# MCU.net
KiCad netlist of a schematic drawn in Altium Designer
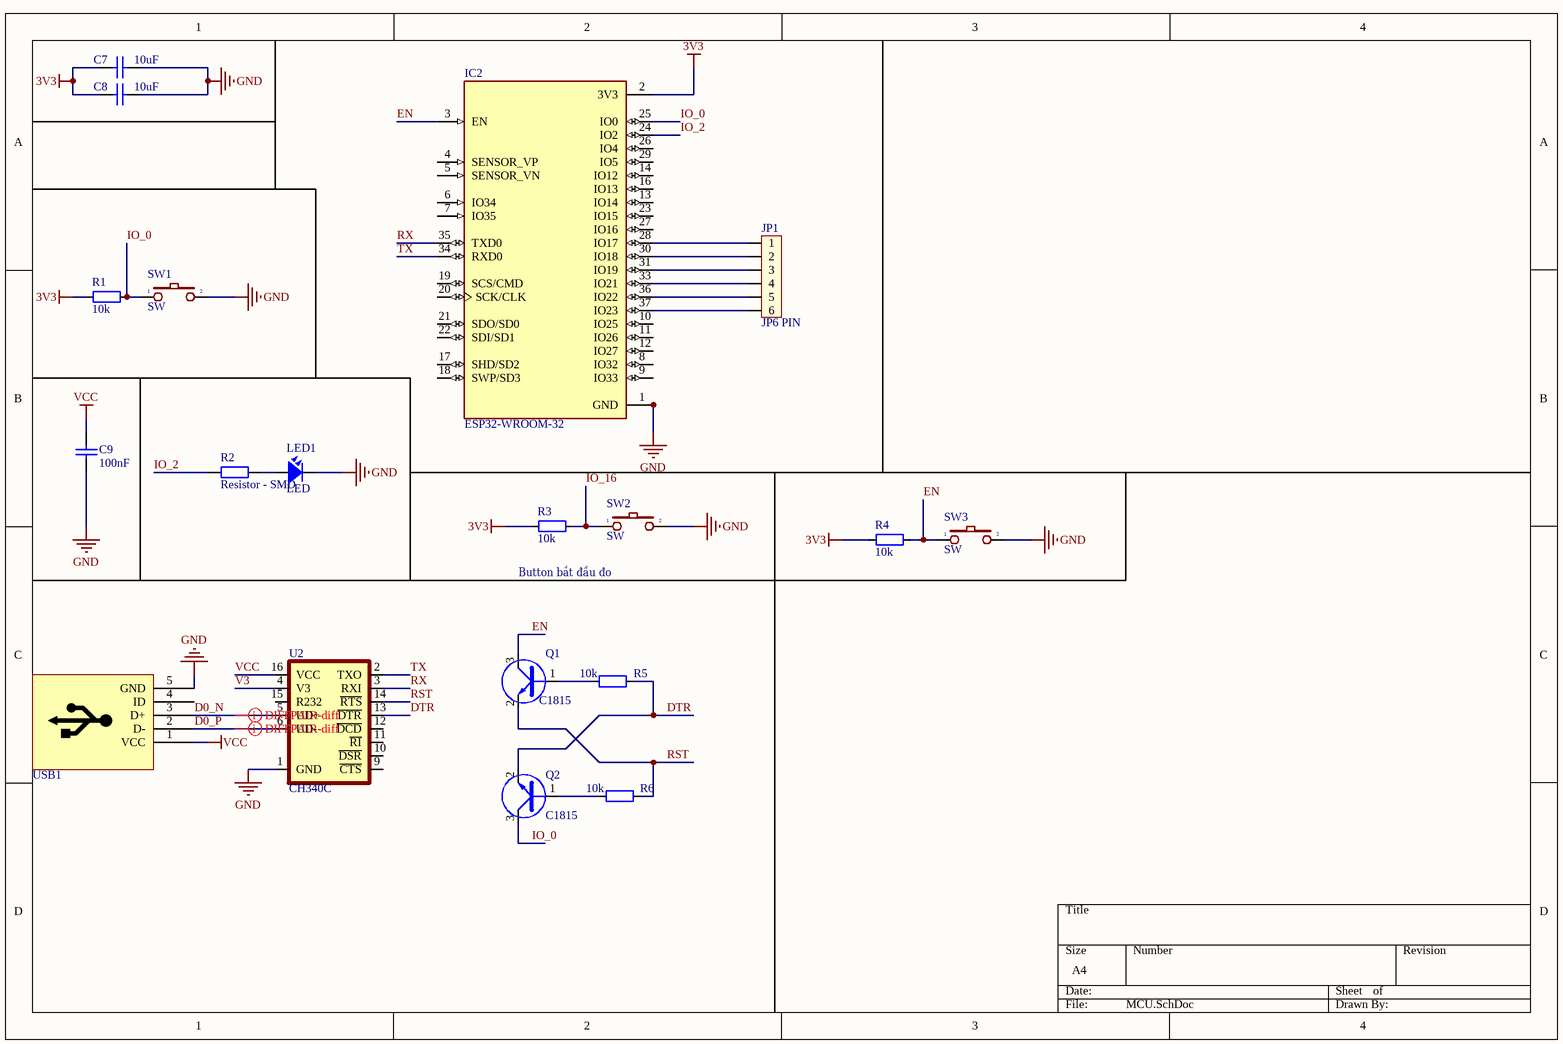
[diagram p0: MCU.SchDoc]

(export (version "E")
  (design (tool "Eeschema 10.0.6"))
  (components
    (comp (ref "C7")
      (value "10uF")
      (footprint "C0805")
      (description "Capacitor")
      (fields (field (name "PUBLISHER") "Altium Limited"))
      (libsource (lib "My Library") (part "CapSMD"))
    )
    (comp (ref "C8")
      (value "10uF")
      (footprint "C0805")
      (description "Capacitor")
      (fields (field (name "PUBLISHER") "Altium Limited"))
      (libsource (lib "My Library") (part "CapSMD"))
    )
    (comp (ref "C9")
      (value "100nF")
      (footprint "C0805")
      (description "Capacitor")
      (fields (field (name "PUBLISHER") "Altium Limited"))
      (libsource (lib "My Library") (part "CapSMD"))
    )
    (comp (ref "IC2")
      (value "ESP32-WROOM-32")
      (footprint "MODULE_ESP32-WROOM-32")
      (description "Bluetooth, WiFi Transceiver Module 2.4GHz ~ 2.5GHz Surface Mount")
      (fields (field (name "MF") "Espressif Systems") (field (name "DIGI-KEY_PART_NUMBER") "1904-1010-1-ND"))
      (libsource (lib "Main") (part "ESP32-WROOM-32"))
    )
    (comp (ref "JP1") (value "JP6 PIN") (footprint "JP6") (libsource (lib "Main") (part "JP6")))
    (comp (ref "LED1")
      (value "LED")
      (footprint "LED0805")
      (description "LED Single colour Green and Red")
      (libsource (lib "Main") (part "LED"))
    )
    (comp (ref "Q1")
      (value "C1815")
      (footprint "SOT23D")
      (description "NPN 600mW, ECB")
      (libsource (lib "My Library") (part "2SC1815"))
    )
    (comp (ref "Q2")
      (value "C1815")
      (footprint "SOT23D")
      (description "NPN 600mW, ECB")
      (libsource (lib "") (part "2SC1815_1"))
    )
    (comp (ref "R1")
      (value "10k")
      (footprint "RES-SMD-0805")
      (description "Resistor")
      (fields
        (field (name "MANUFACTURER") "Generic Components")
        (field (name "PUBLISHER") "Altium Hobart Technology Centre")
      )
      (libsource (lib "My Library") (part "Resistor - SMD"))
    )
    (comp (ref "R2")
      (value "Resistor - SMD")
      (footprint "RES-SMD-0805")
      (description "Resistor SMD")
      (fields
        (field (name "MANUFACTURER") "Generic Components")
        (field (name "PUBLISHER") "Altium Hobart Technology Centre")
      )
      (libsource (lib "Main") (part "Resistor - SMD"))
    )
    (comp (ref "R3")
      (value "10k")
      (footprint "RES-SMD-0805")
      (description "Resistor")
      (fields
        (field (name "MANUFACTURER") "Generic Components")
        (field (name "PUBLISHER") "Altium Hobart Technology Centre")
      )
      (libsource (lib "My Library") (part "Resistor - SMD"))
    )
    (comp (ref "R4")
      (value "10k")
      (footprint "RES-SMD-0805")
      (description "Resistor")
      (fields
        (field (name "MANUFACTURER") "Generic Components")
        (field (name "PUBLISHER") "Altium Hobart Technology Centre")
      )
      (libsource (lib "My Library") (part "Resistor - SMD"))
    )
    (comp (ref "R5")
      (value "10k")
      (footprint "RES-SMD-0805")
      (description "Resistor")
      (fields
        (field (name "MANUFACTURER") "Generic Components")
        (field (name "PUBLISHER") "Altium Hobart Technology Centre")
      )
      (libsource (lib "My Library") (part "Resistor - SMD"))
    )
    (comp (ref "R6")
      (value "10k")
      (footprint "RES-SMD-0805")
      (description "Resistor")
      (fields
        (field (name "MANUFACTURER") "Generic Components")
        (field (name "PUBLISHER") "Altium Hobart Technology Centre")
      )
      (libsource (lib "My Library") (part "Resistor - SMD"))
    )
    (comp (ref "SW1")
      (value "SW")
      (footprint "SW2")
      (description "Switch button 2 pin")
      (libsource (lib "My Library") (part "SW2"))
    )
    (comp (ref "SW2")
      (value "SW")
      (footprint "SW2")
      (description "Switch button 2 pin")
      (libsource (lib "My Library") (part "SW2"))
    )
    (comp (ref "SW3")
      (value "SW")
      (footprint "SW2")
      (description "Switch button 2 pin")
      (libsource (lib "My Library") (part "SW2"))
    )
    (comp (ref "U2")
      (value "CH340C")
      (footprint "SOP-16")
      (description "USB to serial chip CH340")
      (fields (field (name "MF") "WCH"))
      (libsource (lib "My Library") (part "CH340C"))
    )
    (comp (ref "USB1") (value "USB") (footprint "USB-M1") (libsource (lib "My Library") (part "USB-M")))
  )
  (nets
    (net (code "1") (name "/D0_N") (class "Default")
      (node (ref "U2") (pin "5") (pinfunction "UD+_5") (pintype "bidirectional"))
      (node (ref "USB1") (pin "3") (pinfunction "D+_3") (pintype "passive"))
    )
    (net (code "2") (name "/D0_P") (class "Default")
      (node (ref "U2") (pin "6") (pinfunction "UD-_6") (pintype "bidirectional"))
      (node (ref "USB1") (pin "2") (pinfunction "D-_2") (pintype "passive"))
    )
    (net (code "3") (name "/DTR") (class "Default")
      (node (ref "Q2") (pin "2") (pinfunction "E_2") (pintype "passive"))
      (node (ref "R5") (pin "1") (pinfunction "1_1") (pintype "passive"))
      (node (ref "U2") (pin "13") (pinfunction "~{DTR}_13") (pintype "bidirectional"))
    )
    (net (code "4") (name "/EN") (class "Default")
      (node (ref "IC2") (pin "3") (pinfunction "EN_3") (pintype "input"))
      (node (ref "Q1") (pin "3") (pinfunction "C_3") (pintype "passive"))
      (node (ref "R4") (pin "1") (pinfunction "1_1") (pintype "passive"))
      (node (ref "SW3") (pin "1") (pinfunction "1_1") (pintype "passive"))
    )
    (net (code "5") (name "/IO_0") (class "Default")
      (node (ref "IC2") (pin "25") (pinfunction "IO0_25") (pintype "bidirectional"))
      (node (ref "Q2") (pin "3") (pinfunction "C_3") (pintype "passive"))
      (node (ref "R1") (pin "1") (pinfunction "1_1") (pintype "passive"))
      (node (ref "SW1") (pin "1") (pinfunction "1_1") (pintype "passive"))
    )
    (net (code "6") (name "/IO_2") (class "Default")
      (node (ref "IC2") (pin "24") (pinfunction "IO2_24") (pintype "bidirectional"))
      (node (ref "R2") (pin "2") (pinfunction "2_2") (pintype "passive"))
    )
    (net (code "7") (name "/IO_16") (class "Default")
      (node (ref "R3") (pin "1") (pinfunction "1_1") (pintype "passive"))
      (node (ref "SW2") (pin "1") (pinfunction "1_1") (pintype "passive"))
    )
    (net (code "8") (name "/RST") (class "Default")
      (node (ref "Q1") (pin "2") (pinfunction "E_2") (pintype "passive"))
      (node (ref "R6") (pin "1") (pinfunction "1_1") (pintype "passive"))
      (node (ref "U2") (pin "14") (pinfunction "~{RTS}_14") (pintype "bidirectional"))
    )
    (net (code "9") (name "/RX") (class "Default")
      (node (ref "IC2") (pin "35") (pinfunction "TXD0_35") (pintype "bidirectional"))
      (node (ref "U2") (pin "3") (pinfunction "RXI_3") (pintype "bidirectional"))
    )
    (net (code "10") (name "/TX") (class "Default")
      (node (ref "IC2") (pin "34") (pinfunction "RXD0_34") (pintype "bidirectional"))
      (node (ref "U2") (pin "2") (pinfunction "TXO_2") (pintype "bidirectional"))
    )
    (net (code "11") (name "/V3") (class "Default")
      (node (ref "U2") (pin "4") (pinfunction "V3_4") (pintype "bidirectional"))
    )
    (net (code "12") (name "3V3") (class "Default")
      (node (ref "C7") (pin "1") (pinfunction "1_1") (pintype "passive"))
      (node (ref "C8") (pin "1") (pinfunction "1_1") (pintype "passive"))
      (node (ref "IC2") (pin "2") (pinfunction "3V3_2") (pintype "power_in"))
      (node (ref "R1") (pin "2") (pinfunction "2_2") (pintype "passive"))
      (node (ref "R3") (pin "2") (pinfunction "2_2") (pintype "passive"))
      (node (ref "R4") (pin "2") (pinfunction "2_2") (pintype "passive"))
    )
    (net (code "13") (name "GND") (class "Default")
      (node (ref "C7") (pin "2") (pinfunction "2_2") (pintype "passive"))
      (node (ref "C8") (pin "2") (pinfunction "2_2") (pintype "passive"))
      (node (ref "C9") (pin "1") (pinfunction "1_1") (pintype "passive"))
      (node (ref "IC2") (pin "1") (pinfunction "GND_1") (pintype "power_in"))
      (node (ref "IC2") (pin "15") (pinfunction "GND_15") (pintype "power_in"))
      (node (ref "IC2") (pin "38") (pinfunction "GND_38") (pintype "power_in"))
      (node (ref "IC2") (pin "39_1") (pinfunction "GND_39_1") (pintype "power_in"))
      (node (ref "IC2") (pin "39_10") (pinfunction "GND_39_10") (pintype "power_in"))
      (node (ref "IC2") (pin "39_11") (pinfunction "GND_39_11") (pintype "power_in"))
      (node (ref "IC2") (pin "39_12") (pinfunction "GND_39_12") (pintype "power_in"))
      (node (ref "IC2") (pin "39_13") (pinfunction "GND_39_13") (pintype "power_in"))
      (node (ref "IC2") (pin "39_14") (pinfunction "GND_39_14") (pintype "power_in"))
      (node (ref "IC2") (pin "39_15") (pinfunction "GND_39_15") (pintype "power_in"))
      (node (ref "IC2") (pin "39_16") (pinfunction "GND_39_16") (pintype "power_in"))
      (node (ref "IC2") (pin "39_17") (pinfunction "GND_39_17") (pintype "power_in"))
      (node (ref "IC2") (pin "39_18") (pinfunction "GND_39_18") (pintype "power_in"))
      (node (ref "IC2") (pin "39_19") (pinfunction "GND_39_19") (pintype "power_in"))
      (node (ref "IC2") (pin "39_2") (pinfunction "GND_39_2") (pintype "power_in"))
      (node (ref "IC2") (pin "39_20") (pinfunction "GND_39_20") (pintype "power_in"))
      (node (ref "IC2") (pin "39_21") (pinfunction "GND_39_21") (pintype "power_in"))
      (node (ref "IC2") (pin "39_3") (pinfunction "GND_39_3") (pintype "power_in"))
      (node (ref "IC2") (pin "39_4") (pinfunction "GND_39_4") (pintype "power_in"))
      (node (ref "IC2") (pin "39_5") (pinfunction "GND_39_5") (pintype "power_in"))
      (node (ref "IC2") (pin "39_6") (pinfunction "GND_39_6") (pintype "power_in"))
      (node (ref "IC2") (pin "39_7") (pinfunction "GND_39_7") (pintype "power_in"))
      (node (ref "IC2") (pin "39_8") (pinfunction "GND_39_8") (pintype "power_in"))
      (node (ref "IC2") (pin "39_9") (pinfunction "GND_39_9") (pintype "power_in"))
      (node (ref "LED1") (pin "2") (pinfunction "2_2") (pintype "passive"))
      (node (ref "SW1") (pin "2") (pinfunction "2_2") (pintype "passive"))
      (node (ref "SW2") (pin "2") (pinfunction "2_2") (pintype "passive"))
      (node (ref "SW3") (pin "2") (pinfunction "2_2") (pintype "passive"))
      (node (ref "U2") (pin "1") (pinfunction "GND_1") (pintype "bidirectional"))
      (node (ref "USB1") (pin "5") (pinfunction "GND_5") (pintype "passive"))
    )
    (net (code "14") (name "Net-(IC2-IO17)") (class "Default")
      (node (ref "IC2") (pin "28") (pinfunction "IO17_28") (pintype "bidirectional"))
      (node (ref "JP1") (pin "1") (pinfunction "1_1") (pintype "passive"))
    )
    (net (code "15") (name "Net-(IC2-IO18)") (class "Default")
      (node (ref "IC2") (pin "30") (pinfunction "IO18_30") (pintype "bidirectional"))
      (node (ref "JP1") (pin "2") (pinfunction "2_2") (pintype "passive"))
    )
    (net (code "16") (name "Net-(IC2-IO19)") (class "Default")
      (node (ref "IC2") (pin "31") (pinfunction "IO19_31") (pintype "bidirectional"))
      (node (ref "JP1") (pin "3") (pinfunction "3_3") (pintype "passive"))
    )
    (net (code "17") (name "Net-(IC2-IO21)") (class "Default")
      (node (ref "IC2") (pin "33") (pinfunction "IO21_33") (pintype "bidirectional"))
      (node (ref "JP1") (pin "4") (pinfunction "4_4") (pintype "passive"))
    )
    (net (code "18") (name "Net-(IC2-IO22)") (class "Default")
      (node (ref "IC2") (pin "36") (pinfunction "IO22_36") (pintype "bidirectional"))
      (node (ref "JP1") (pin "5") (pinfunction "5_5") (pintype "passive"))
    )
    (net (code "19") (name "Net-(IC2-IO23)") (class "Default")
      (node (ref "IC2") (pin "37") (pinfunction "IO23_37") (pintype "bidirectional"))
      (node (ref "JP1") (pin "6") (pinfunction "6_6") (pintype "passive"))
    )
    (net (code "20") (name "Net-(LED1-Pad1)") (class "Default")
      (node (ref "LED1") (pin "1") (pinfunction "1_1") (pintype "passive"))
      (node (ref "R2") (pin "1") (pinfunction "1_1") (pintype "passive"))
    )
    (net (code "21") (name "Net-(Q1-B)") (class "Default")
      (node (ref "Q1") (pin "1") (pinfunction "B_1") (pintype "passive"))
      (node (ref "R5") (pin "2") (pinfunction "2_2") (pintype "passive"))
    )
    (net (code "22") (name "Net-(Q2-B)") (class "Default")
      (node (ref "Q2") (pin "1") (pinfunction "B_1") (pintype "passive"))
      (node (ref "R6") (pin "2") (pinfunction "2_2") (pintype "passive"))
    )
    (net (code "23") (name "VCC") (class "Default")
      (node (ref "C9") (pin "2") (pinfunction "2_2") (pintype "passive"))
      (node (ref "U2") (pin "16") (pinfunction "VCC_16") (pintype "bidirectional"))
      (node (ref "USB1") (pin "1") (pinfunction "VCC_1") (pintype "passive"))
    )
    (net (code "24") (name "unconnected-(IC2-IO4-Pad26)") (class "Default")
      (node (ref "IC2") (pin "26") (pinfunction "IO4_26") (pintype "bidirectional"))
    )
    (net (code "25") (name "unconnected-(IC2-IO5-Pad29)") (class "Default")
      (node (ref "IC2") (pin "29") (pinfunction "IO5_29") (pintype "bidirectional"))
    )
    (net (code "26") (name "unconnected-(IC2-IO12-Pad14)") (class "Default")
      (node (ref "IC2") (pin "14") (pinfunction "IO12_14") (pintype "bidirectional"))
    )
    (net (code "27") (name "unconnected-(IC2-IO13-Pad16)") (class "Default")
      (node (ref "IC2") (pin "16") (pinfunction "IO13_16") (pintype "bidirectional"))
    )
    (net (code "28") (name "unconnected-(IC2-IO14-Pad13)") (class "Default")
      (node (ref "IC2") (pin "13") (pinfunction "IO14_13") (pintype "bidirectional"))
    )
    (net (code "29") (name "unconnected-(IC2-IO15-Pad23)") (class "Default")
      (node (ref "IC2") (pin "23") (pinfunction "IO15_23") (pintype "bidirectional"))
    )
    (net (code "30") (name "unconnected-(IC2-IO16-Pad27)") (class "Default")
      (node (ref "IC2") (pin "27") (pinfunction "IO16_27") (pintype "bidirectional"))
    )
    (net (code "31") (name "unconnected-(IC2-IO25-Pad10)") (class "Default")
      (node (ref "IC2") (pin "10") (pinfunction "IO25_10") (pintype "bidirectional"))
    )
    (net (code "32") (name "unconnected-(IC2-IO26-Pad11)") (class "Default")
      (node (ref "IC2") (pin "11") (pinfunction "IO26_11") (pintype "bidirectional"))
    )
    (net (code "33") (name "unconnected-(IC2-IO27-Pad12)") (class "Default")
      (node (ref "IC2") (pin "12") (pinfunction "IO27_12") (pintype "bidirectional"))
    )
    (net (code "34") (name "unconnected-(IC2-IO32-Pad8)") (class "Default")
      (node (ref "IC2") (pin "8") (pinfunction "IO32_8") (pintype "bidirectional"))
    )
    (net (code "35") (name "unconnected-(IC2-IO33-Pad9)") (class "Default")
      (node (ref "IC2") (pin "9") (pinfunction "IO33_9") (pintype "bidirectional"))
    )
    (net (code "36") (name "unconnected-(IC2-IO34-Pad6)") (class "Default")
      (node (ref "IC2") (pin "6") (pinfunction "IO34_6") (pintype "input"))
    )
    (net (code "37") (name "unconnected-(IC2-IO35-Pad7)") (class "Default")
      (node (ref "IC2") (pin "7") (pinfunction "IO35_7") (pintype "input"))
    )
    (net (code "38") (name "unconnected-(IC2-SCK{slash}CLK-Pad20)") (class "Default")
      (node (ref "IC2") (pin "20") (pinfunction "SCK/CLK_20") (pintype "bidirectional"))
    )
    (net (code "39") (name "unconnected-(IC2-SCS{slash}CMD-Pad19)") (class "Default")
      (node (ref "IC2") (pin "19") (pinfunction "SCS/CMD_19") (pintype "bidirectional"))
    )
    (net (code "40") (name "unconnected-(IC2-SDI{slash}SD1-Pad22)") (class "Default")
      (node (ref "IC2") (pin "22") (pinfunction "SDI/SD1_22") (pintype "bidirectional"))
    )
    (net (code "41") (name "unconnected-(IC2-SDO{slash}SD0-Pad21)") (class "Default")
      (node (ref "IC2") (pin "21") (pinfunction "SDO/SD0_21") (pintype "bidirectional"))
    )
    (net (code "42") (name "unconnected-(IC2-SENSOR_VN-Pad5)") (class "Default")
      (node (ref "IC2") (pin "5") (pinfunction "SENSOR_VN_5") (pintype "input"))
    )
    (net (code "43") (name "unconnected-(IC2-SENSOR_VP-Pad4)") (class "Default")
      (node (ref "IC2") (pin "4") (pinfunction "SENSOR_VP_4") (pintype "input"))
    )
    (net (code "44") (name "unconnected-(IC2-SHD{slash}SD2-Pad17)") (class "Default")
      (node (ref "IC2") (pin "17") (pinfunction "SHD/SD2_17") (pintype "bidirectional"))
    )
    (net (code "45") (name "unconnected-(IC2-SWP{slash}SD3-Pad18)") (class "Default")
      (node (ref "IC2") (pin "18") (pinfunction "SWP/SD3_18") (pintype "bidirectional"))
    )
    (net (code "46") (name "unconnected-(U2-R232-Pad15)") (class "Default")
      (node (ref "U2") (pin "15") (pinfunction "R232_15") (pintype "bidirectional"))
    )
    (net (code "47") (name "unconnected-(U2-~{CTS}-Pad9)") (class "Default")
      (node (ref "U2") (pin "9") (pinfunction "~{CTS}_9") (pintype "bidirectional"))
    )
    (net (code "48") (name "unconnected-(U2-~{DCD}-Pad12)") (class "Default")
      (node (ref "U2") (pin "12") (pinfunction "~{DCD}_12") (pintype "bidirectional"))
    )
    (net (code "49") (name "unconnected-(U2-~{DSR}-Pad10)") (class "Default")
      (node (ref "U2") (pin "10") (pinfunction "~{DSR}_10") (pintype "bidirectional"))
    )
    (net (code "50") (name "unconnected-(U2-~{RI}-Pad11)") (class "Default")
      (node (ref "U2") (pin "11") (pinfunction "~{RI}_11") (pintype "bidirectional"))
    )
    (net (code "51") (name "unconnected-(USB1-ID-Pad4)") (class "Default")
      (node (ref "USB1") (pin "4") (pinfunction "ID_4") (pintype "passive"))
    )
  )
)
